# Arachnio.net
KiCad netlist of a schematic drawn in EAGLE
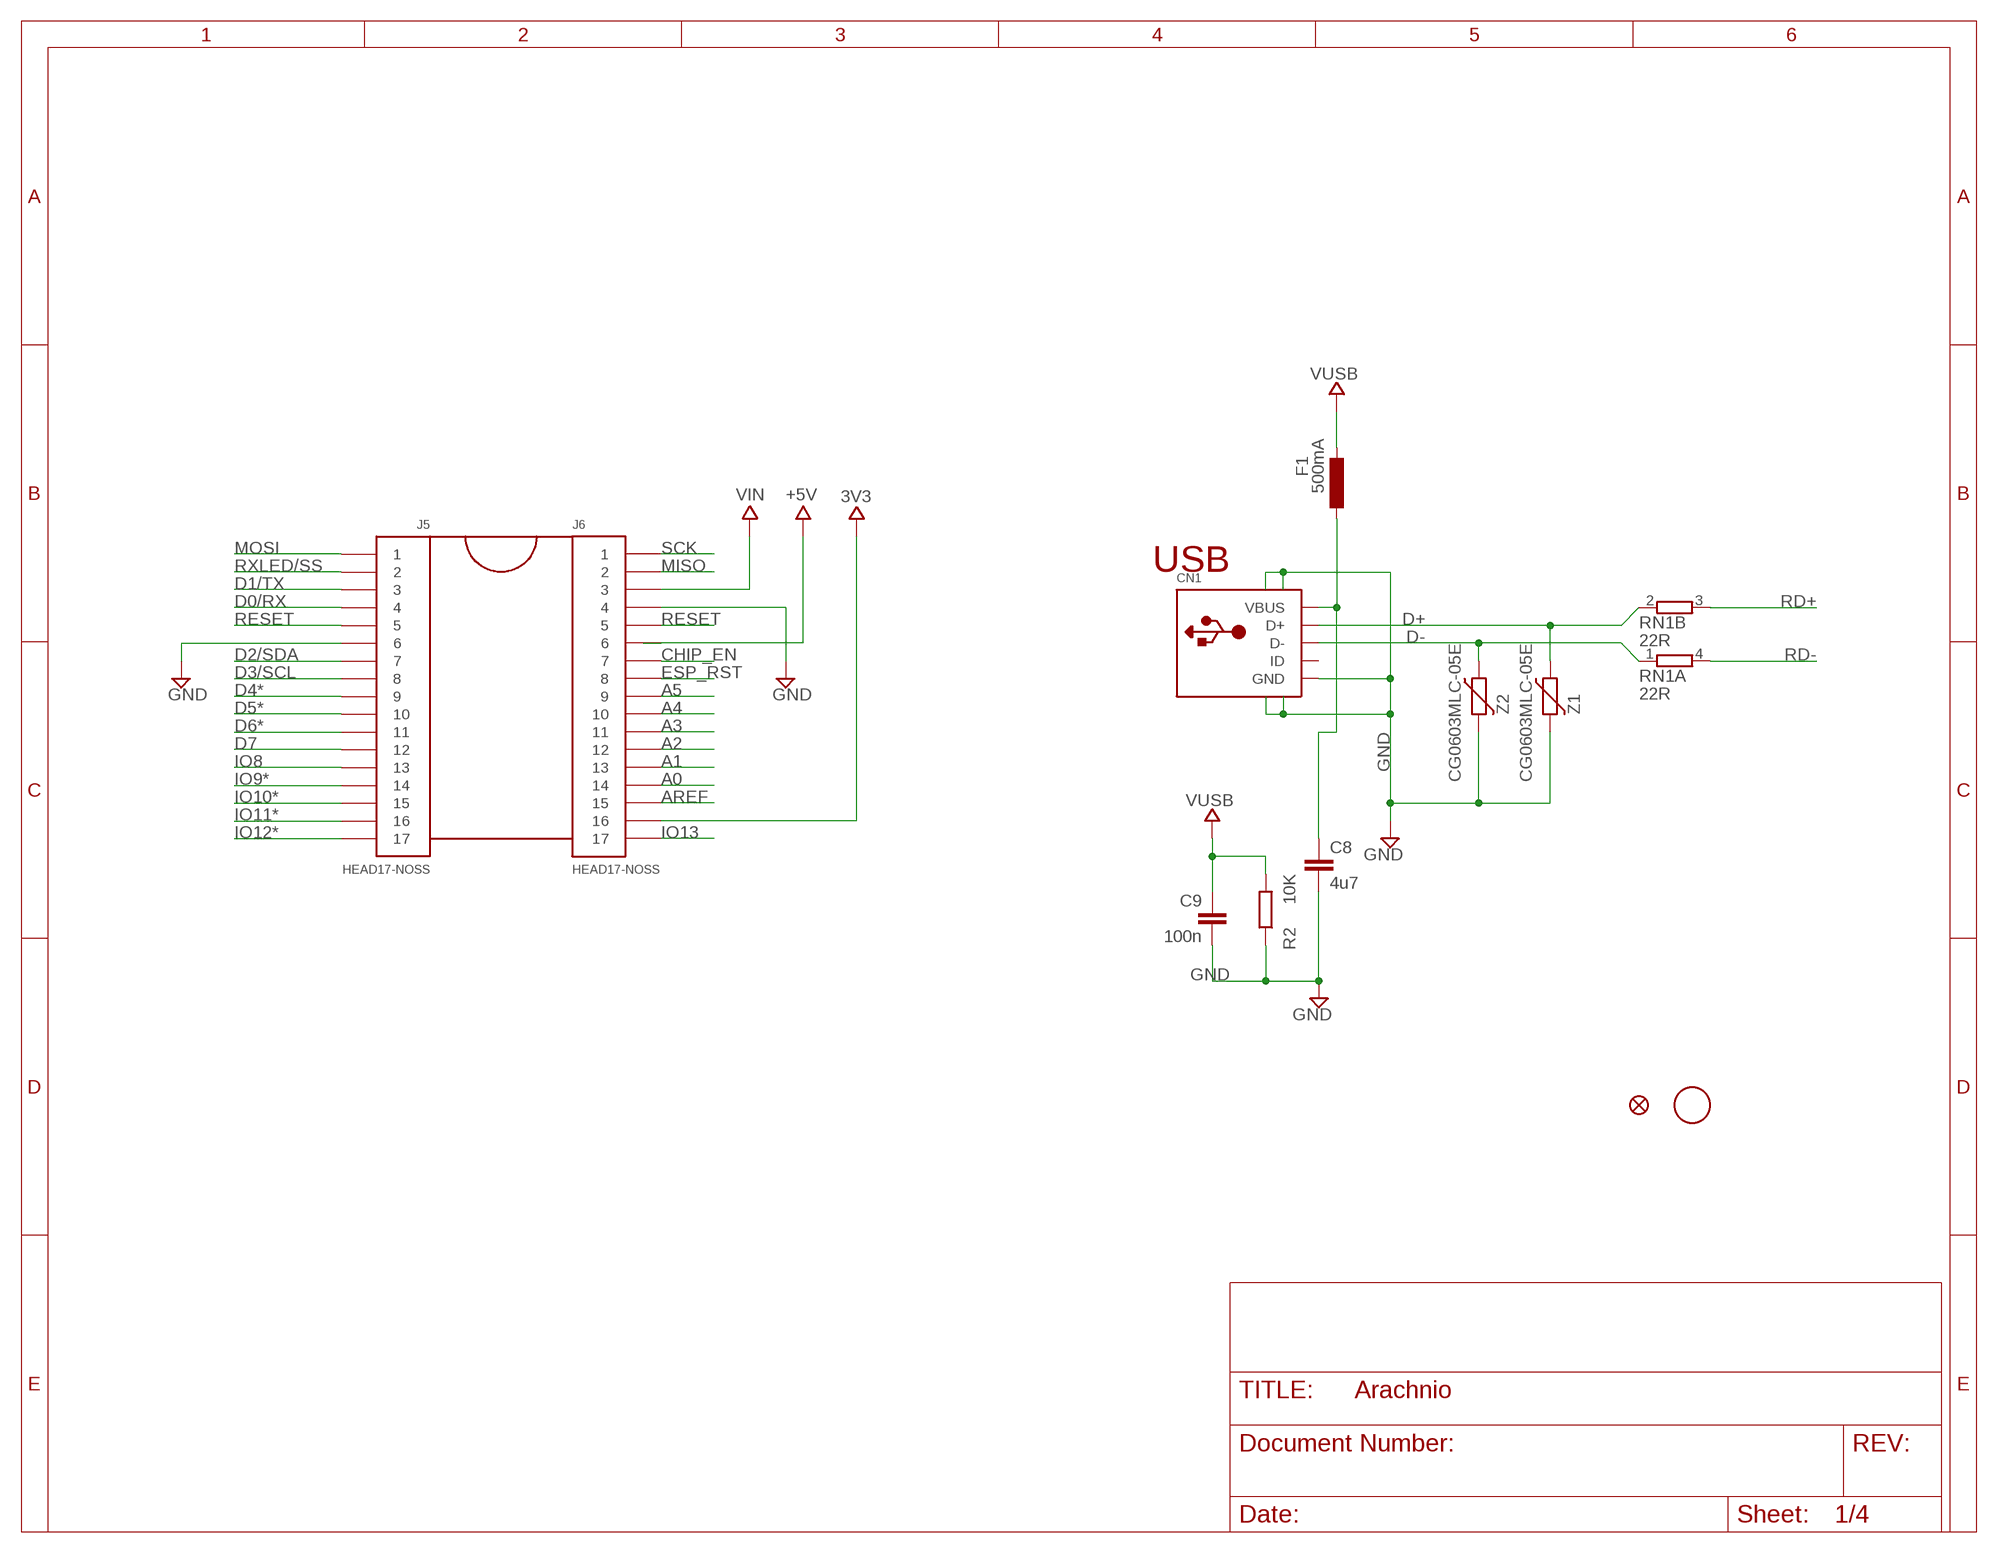
[diagram p0: schematic, sheet 1]
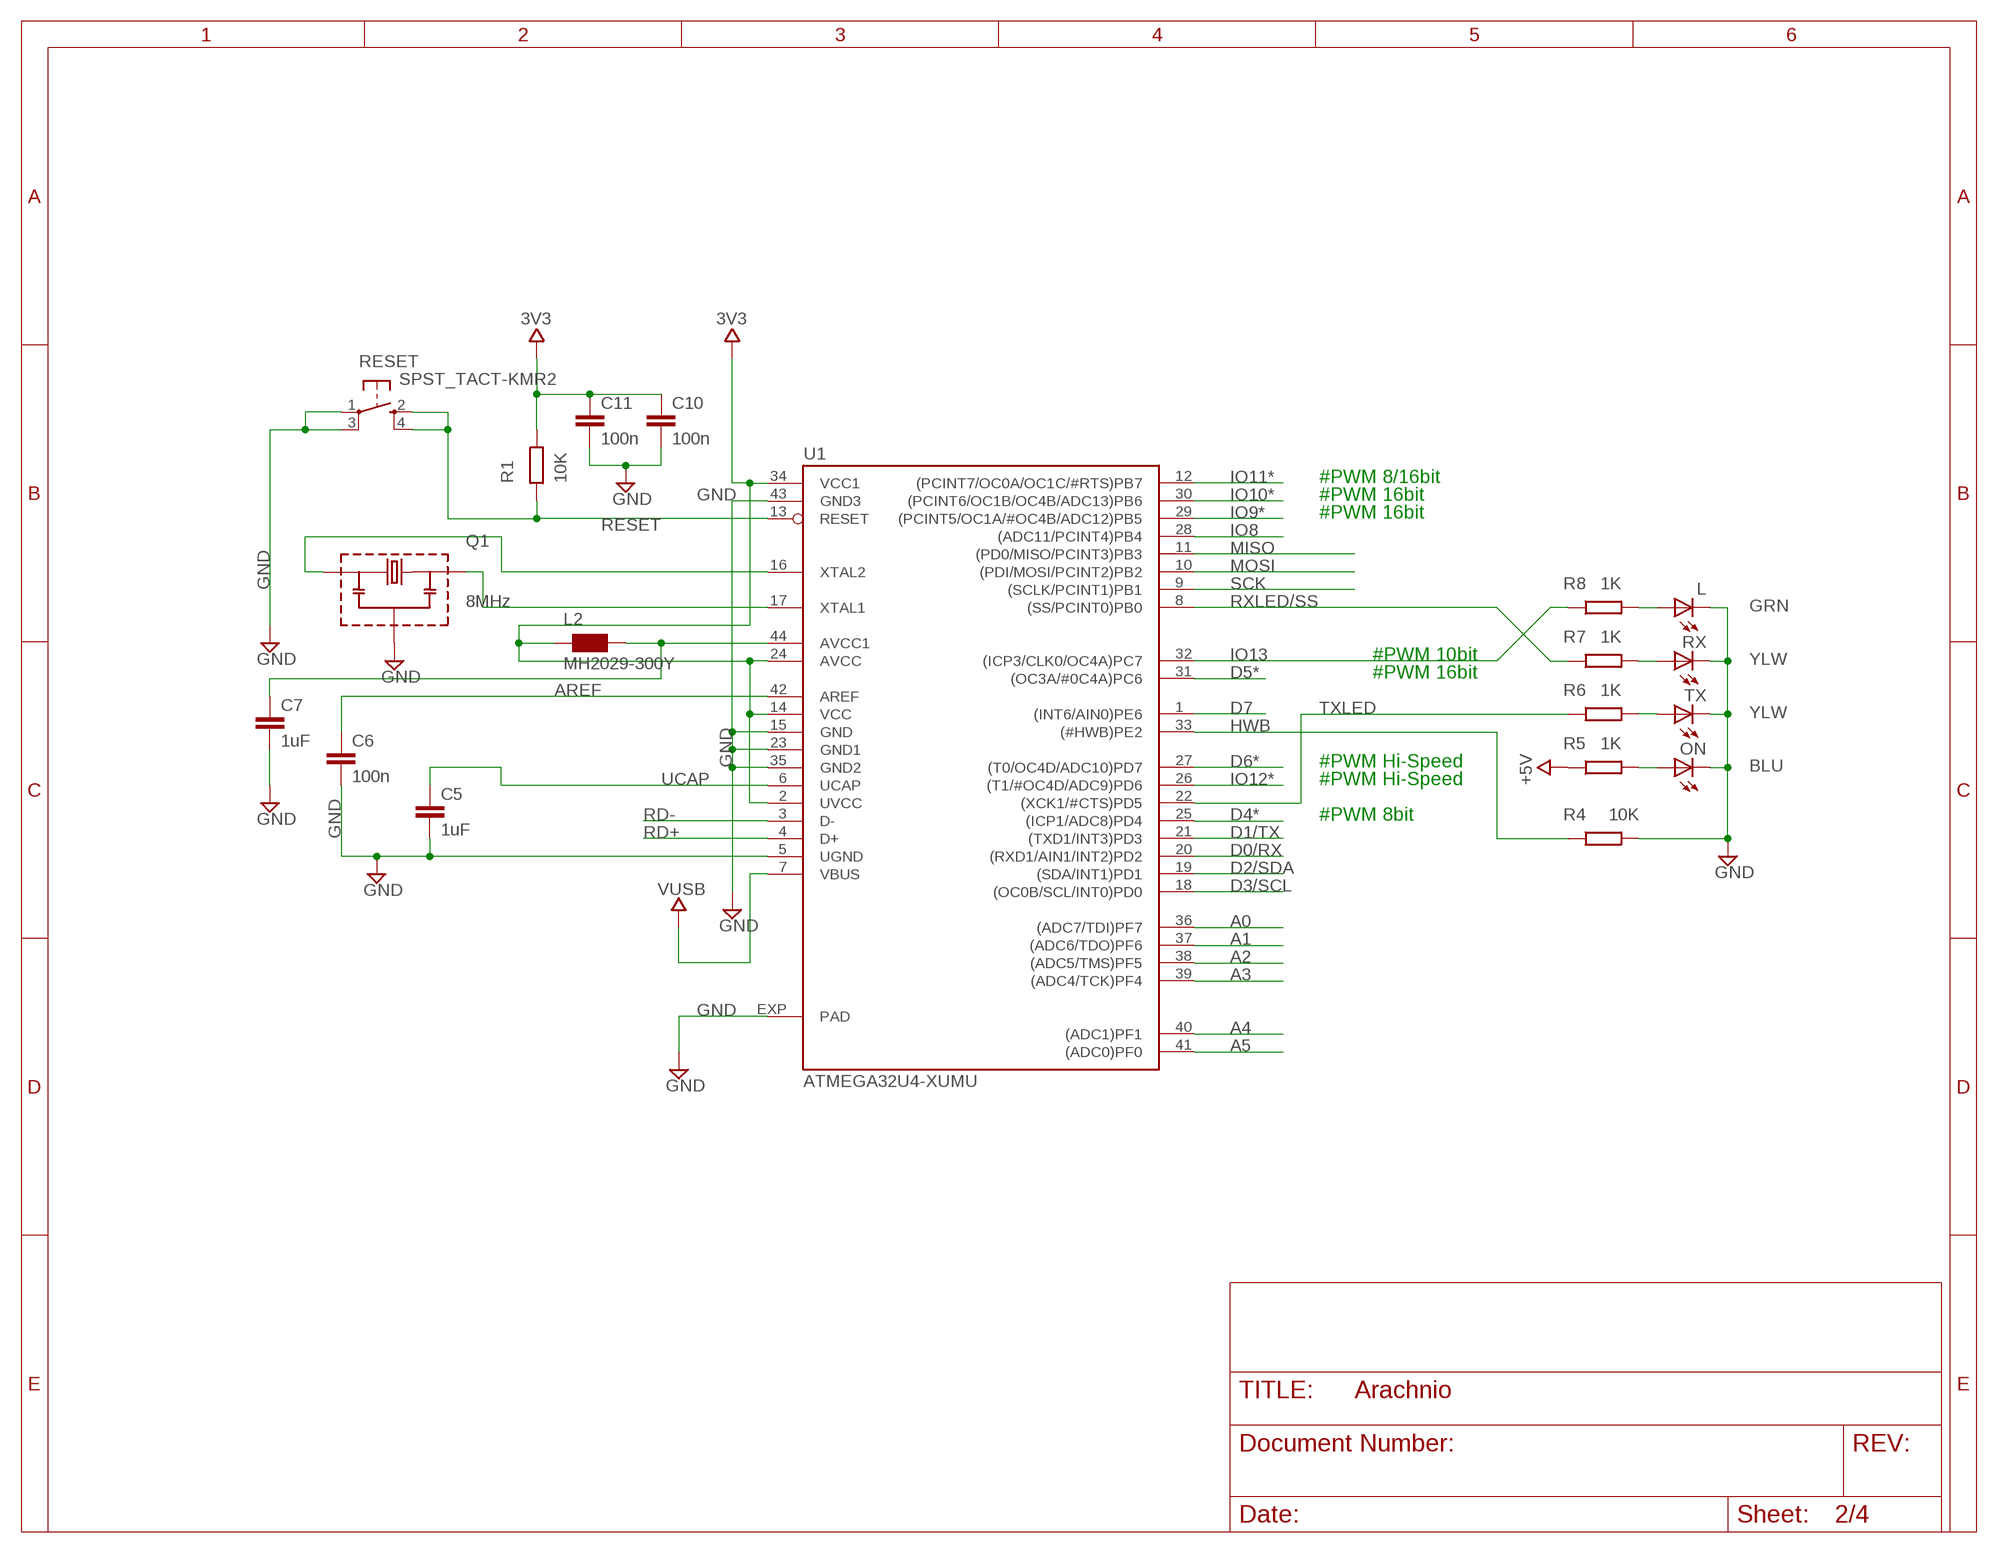
[diagram p1: schematic, sheet 2]
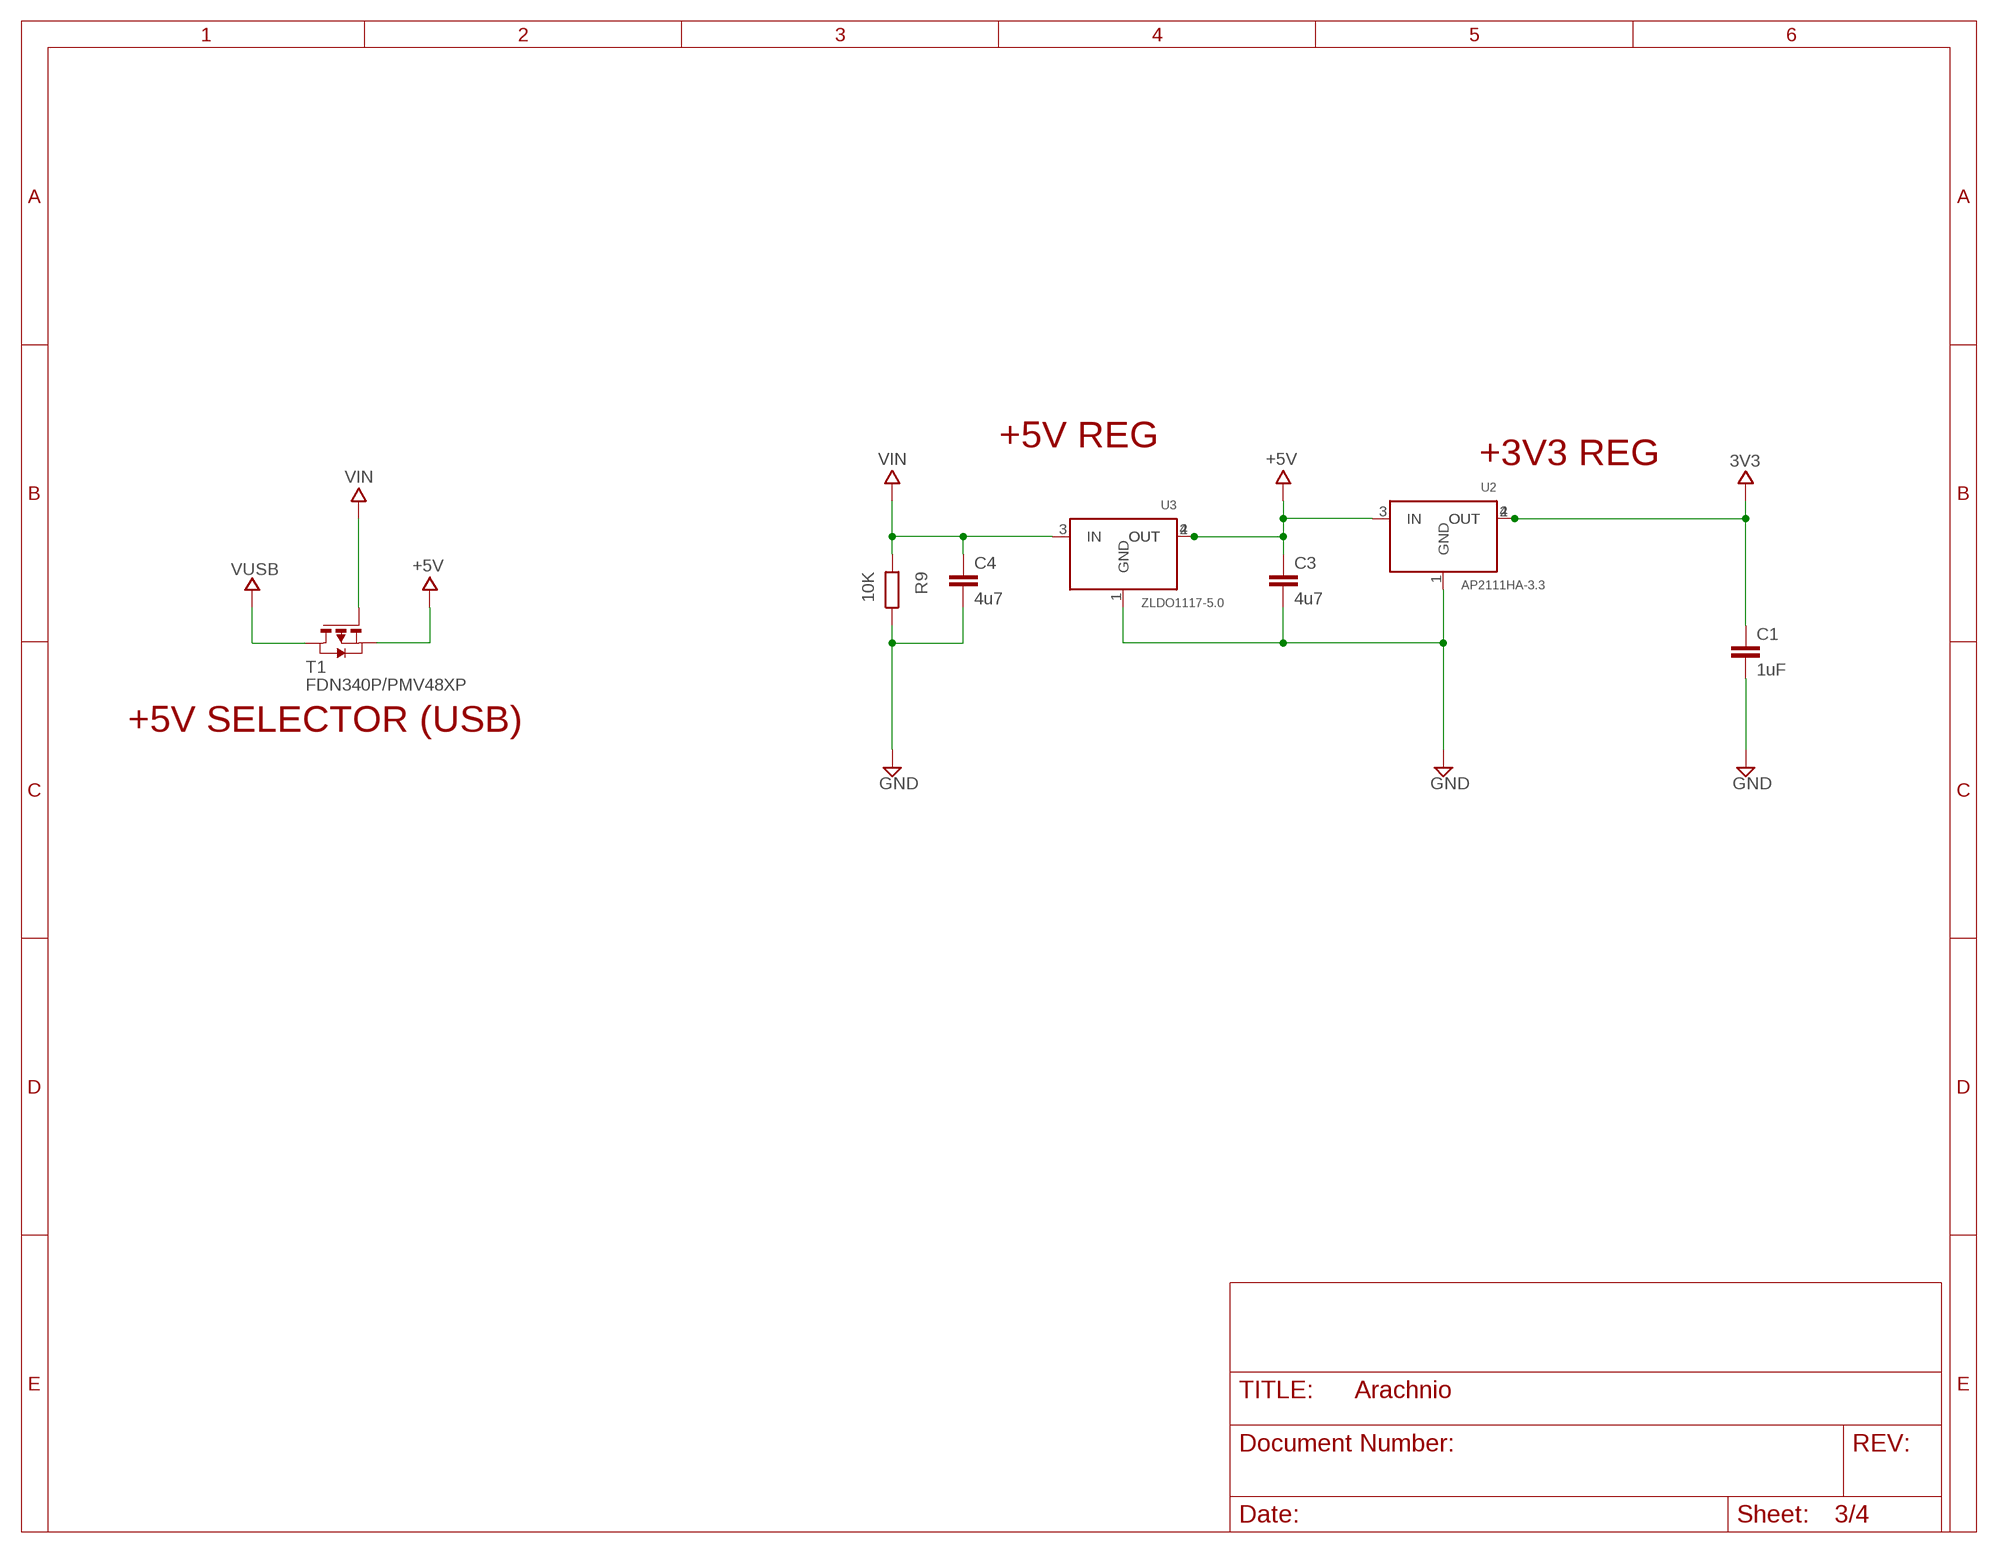
[diagram p2: schematic, sheet 3]
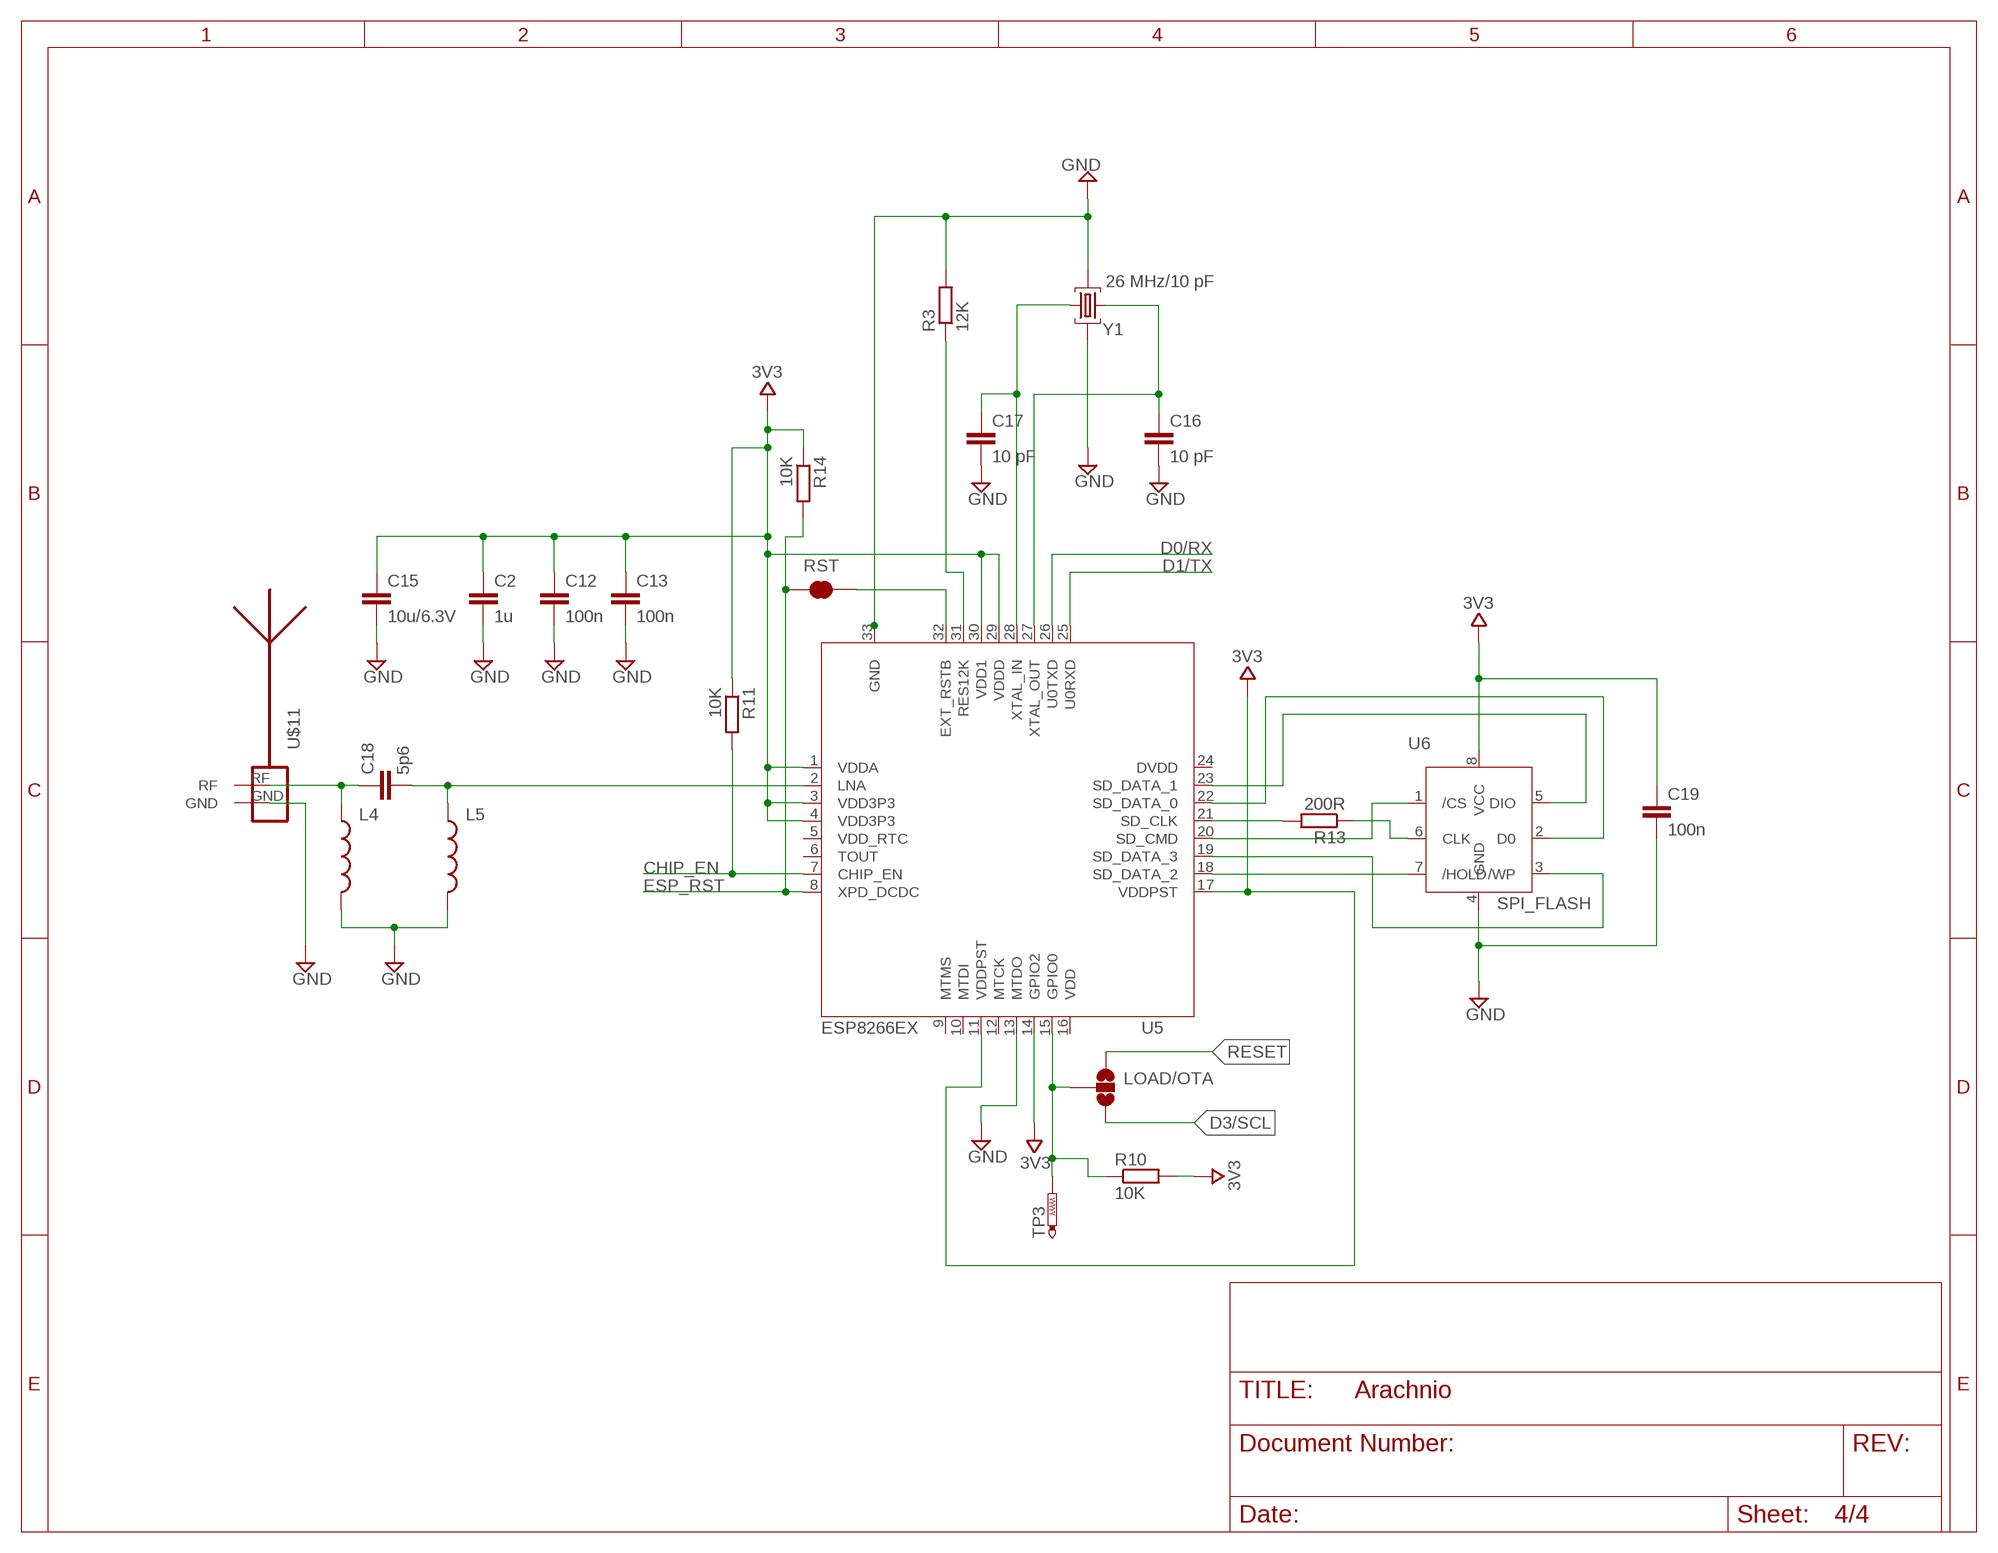
[diagram p3: schematic, sheet 4]

(export (version "E")
  (design (tool "Eeschema 10.0.6"))
  (components
    (comp (ref "C1")
      (value "1uF")
      (footprint "eagle-import:C0603")
      (fields (field (name "PARTNO") "C0603C105K3PACTU"))
      (libsource (lib "eagle-import") (part "C-EUC0603"))
    )
    (comp (ref "C3")
      (value "4u7")
      (footprint "eagle-import:C0603")
      (fields (field (name "PARTNO") "CL10A475KA8NQNC"))
      (libsource (lib "eagle-import") (part "C-EUC0603"))
    )
    (comp (ref "C4")
      (value "4u7")
      (footprint "eagle-import:C0603")
      (fields (field (name "PARTNO") "CL10A475KA8NQNC"))
      (libsource (lib "eagle-import") (part "C-EUC0603"))
    )
    (comp (ref "R9")
      (value "10K")
      (footprint "eagle-import:R0603")
      (fields (field (name "PARTNO") "RNCP0603FTD10K0"))
      (libsource (lib "eagle-import") (part "R-EU_R0603"))
    )
    (comp (ref "T1")
      (value "FDN340P/PMV48XP")
      (footprint "eagle-import:SOT-23")
      (fields (field (name "PARTNO") "FDN340P"))
      (libsource (lib "eagle-import") (part "PMOSSOT23"))
    )
    (comp (ref "U2")
      (value "AP2111HA-3.3")
      (footprint "eagle-import:SOT223")
      (fields (field (name "PARTNO") "AP2111H-3.3TRG1"))
      (libsource (lib "eagle-import") (part "AP2111HA-3.3"))
    )
    (comp (ref "U3")
      (value "ZLDO1117-5.0")
      (footprint "eagle-import:SOT223")
      (fields (field (name "PARTNO") "ZLDO1117G50TA"))
      (libsource (lib "eagle-import") (part "ZLDO1117-5.0"))
    )
    (comp (ref "C2")
      (value "1u")
      (footprint "eagle-import:C0603")
      (fields (field (name "PARTNO") "C0603C105K3PACTU"))
      (libsource (lib "eagle-import") (part "C-EUC0603"))
    )
    (comp (ref "C12")
      (value "100n")
      (footprint "eagle-import:C0603")
      (fields (field (name "PARTNO") "CC0603ZRY5V9BB104"))
      (libsource (lib "eagle-import") (part "C-EUC0603"))
    )
    (comp (ref "C13")
      (value "100n")
      (footprint "eagle-import:C0603")
      (fields (field (name "PARTNO") "CC0603ZRY5V9BB104"))
      (libsource (lib "eagle-import") (part "C-EUC0603"))
    )
    (comp (ref "C15")
      (value "10u/6.3V")
      (footprint "eagle-import:C0603")
      (fields (field (name "PARTNO") "JMK107ABJ106MAHT"))
      (libsource (lib "eagle-import") (part "C-EUC0603"))
    )
    (comp (ref "C16")
      (value "10 pF")
      (footprint "eagle-import:C0603")
      (fields (field (name "PARTNO") "C0603C100K5GACTU"))
      (libsource (lib "eagle-import") (part "C-EUC0603"))
    )
    (comp (ref "C17")
      (value "10 pF")
      (footprint "eagle-import:C0603")
      (fields (field (name "PARTNO") "C0603C100K5GACTU"))
      (libsource (lib "eagle-import") (part "C-EUC0603"))
    )
    (comp (ref "C18")
      (value "5p6")
      (footprint "eagle-import:C0603")
      (fields (field (name "PARTNO") "251R14S5R6CV4T"))
      (libsource (lib "eagle-import") (part "C-EUC0603"))
    )
    (comp (ref "C19")
      (value "100n")
      (footprint "eagle-import:C0603")
      (fields (field (name "PARTNO") "CC0603ZRY5V9BB104"))
      (libsource (lib "eagle-import") (part "C-EUC0603"))
    )
    (comp (ref "L4")
      (value "INDUCTOR0603")
      (footprint "eagle-import:0603")
      (libsource (lib "eagle-import") (part "INDUCTOR0603"))
    )
    (comp (ref "L5")
      (value "INDUCTOR0603")
      (footprint "eagle-import:0603")
      (libsource (lib "eagle-import") (part "INDUCTOR0603"))
    )
    (comp (ref "LOAD/OTA")
      (value "JUMPER-PAD-3-NOYES_SILK")
      (footprint "eagle-import:PAD-JUMPER-3-NO_YES_SILK")
      (libsource (lib "eagle-import") (part "JUMPER-PAD-3-NOYES_SILK"))
    )
    (comp (ref "R3")
      (value "12K")
      (footprint "eagle-import:R0603")
      (fields (field (name "PARTNO") "RMCF0603FT12K0"))
      (libsource (lib "eagle-import") (part "R-EU_R0603"))
    )
    (comp (ref "R10")
      (value "10K")
      (footprint "eagle-import:R0603")
      (fields (field (name "PARTNO") "RNCP0603FTD10K0"))
      (libsource (lib "eagle-import") (part "R-EU_R0603"))
    )
    (comp (ref "R11")
      (value "10K")
      (footprint "eagle-import:R0603")
      (fields (field (name "PARTNO") "RNCP0603FTD10K0"))
      (libsource (lib "eagle-import") (part "R-EU_R0603"))
    )
    (comp (ref "R13")
      (value "200R")
      (footprint "eagle-import:R0603")
      (fields (field (name "PARTNO") "MCR03ERTJ201"))
      (libsource (lib "eagle-import") (part "R-EU_R0603"))
    )
    (comp (ref "R14")
      (value "10K")
      (footprint "eagle-import:R0603")
      (fields (field (name "PARTNO") "RNCP0603FTD10K0"))
      (libsource (lib "eagle-import") (part "R-EU_R0603"))
    )
    (comp (ref "RST")
      (value "JUMPER-PAD-2-NC_BY_TRACE")
      (footprint "eagle-import:PAD-JUMPER-2-NC_BY_TRACE_YES_SILK")
      (libsource (lib "eagle-import") (part "JUMPER-PAD-2-NC_BY_TRACE"))
    )
    (comp (ref "TP3")
      (value "PTR1TP15SQ")
      (footprint "eagle-import:TP15SQ")
      (libsource (lib "eagle-import") (part "PTR1TP15SQ"))
    )
    (comp (ref "U$11")
      (value "ANTENNA_1RIGHT")
      (footprint "eagle-import:SWRA117D_RIGHT")
      (libsource (lib "eagle-import") (part "ANTENNA_1RIGHT"))
    )
    (comp (ref "U5")
      (value "ESP8266EX")
      (footprint "eagle-import:QFN32")
      (libsource (lib "eagle-import") (part "ESP8266EX"))
    )
    (comp (ref "U6")
      (value "SPI_FLASH")
      (footprint "eagle-import:SOIC-8")
      (fields (field (name "PARTNO") "SST25VF512A-33-4C-SAE"))
      (libsource (lib "eagle-import") (part "SPI_FLASH"))
    )
    (comp (ref "Y1")
      (value "26 MHz/10 pF")
      (footprint "eagle-import:CRYSTAL-3.2-2.5")
      (fields (field (name "PARTNO") "403C11A26M00000"))
      (libsource (lib "eagle-import") (part "CRYSTAL-3.2-2.5"))
    )
    (comp (ref "C5")
      (value "1uF")
      (footprint "eagle-import:C0603")
      (fields (field (name "PARTNO") "C0603C105K3PACTU"))
      (libsource (lib "eagle-import") (part "C-EUC0603"))
    )
    (comp (ref "C6")
      (value "100n")
      (footprint "eagle-import:C0603")
      (fields (field (name "PARTNO") "CC0603ZRY5V9BB104"))
      (libsource (lib "eagle-import") (part "C-EUC0603"))
    )
    (comp (ref "C7")
      (value "1uF")
      (footprint "eagle-import:C0603")
      (fields (field (name "PARTNO") "C0603C105K3PACTU"))
      (libsource (lib "eagle-import") (part "C-EUC0603"))
    )
    (comp (ref "C10")
      (value "100n")
      (footprint "eagle-import:C0603")
      (fields (field (name "PARTNO") "CC0603ZRY5V9BB104"))
      (libsource (lib "eagle-import") (part "C-EUC0603"))
    )
    (comp (ref "C11")
      (value "100n")
      (footprint "eagle-import:C0603")
      (fields (field (name "PARTNO") "CC0603ZRY5V9BB104"))
      (libsource (lib "eagle-import") (part "C-EUC0603"))
    )
    (comp (ref "L")
      (value "GRN")
      (footprint "eagle-import:CHIP-LED0603")
      (fields (field (name "PARTNO") "LTST-C191KGKT"))
      (libsource (lib "eagle-import") (part "LEDCHIP-LED0603"))
    )
    (comp (ref "L2")
      (value "MH2029-300Y")
      (footprint "eagle-import:0805")
      (libsource (lib "eagle-import") (part "WE-CBF_0805"))
    )
    (comp (ref "ON")
      (value "BLU")
      (footprint "eagle-import:CHIP-LED0603")
      (fields (field (name "PARTNO") "LB Q39G-L2N2-35-1"))
      (libsource (lib "eagle-import") (part "LEDCHIP-LED0603"))
    )
    (comp (ref "Q1")
      (value "8MHz")
      (footprint "eagle-import:PRQC")
      (fields (field (name "PARTNO") "PRQC8.00CR1010V00L"))
      (libsource (lib "eagle-import") (part "PRQC"))
    )
    (comp (ref "R1")
      (value "10K")
      (footprint "eagle-import:R0603")
      (fields (field (name "PARTNO") "RNCP0603FTD10K0"))
      (libsource (lib "eagle-import") (part "R-EU_R0603"))
    )
    (comp (ref "R4")
      (value "10K")
      (footprint "eagle-import:R0603")
      (fields (field (name "PARTNO") "RNCP0603FTD10K0"))
      (libsource (lib "eagle-import") (part "R-EU_R0603"))
    )
    (comp (ref "R5")
      (value "1K")
      (footprint "eagle-import:R0603")
      (fields (field (name "PARTNO") "RMCF0603FT1K00"))
      (libsource (lib "eagle-import") (part "R-EU_R0603"))
    )
    (comp (ref "R6")
      (value "1K")
      (footprint "eagle-import:R0603")
      (fields (field (name "PARTNO") "RMCF0603FT1K00"))
      (libsource (lib "eagle-import") (part "R-EU_R0603"))
    )
    (comp (ref "R7")
      (value "1K")
      (footprint "eagle-import:R0603")
      (fields (field (name "PARTNO") "RMCF0603FT1K00"))
      (libsource (lib "eagle-import") (part "R-EU_R0603"))
    )
    (comp (ref "R8")
      (value "1K")
      (footprint "eagle-import:R0603")
      (fields (field (name "PARTNO") "RMCF0603FT1K00"))
      (libsource (lib "eagle-import") (part "R-EU_R0603"))
    )
    (comp (ref "RESET")
      (value "SPST_TACT-KMR2")
      (footprint "eagle-import:KMR2")
      (fields (field (name "PARTNO") "KMR221NG"))
      (libsource (lib "eagle-import") (part "SPST_TACT-KMR2"))
    )
    (comp (ref "RX")
      (value "YLW")
      (footprint "eagle-import:CHIP-LED0603")
      (fields (field (name "PARTNO") "LTST-C191KSKT"))
      (libsource (lib "eagle-import") (part "LEDCHIP-LED0603"))
    )
    (comp (ref "TX")
      (value "YLW")
      (footprint "eagle-import:CHIP-LED0603")
      (fields (field (name "PARTNO") "LTST-C191KSKT"))
      (libsource (lib "eagle-import") (part "LEDCHIP-LED0603"))
    )
    (comp (ref "U1")
      (value "ATMEGA32U4-XUMU")
      (footprint "eagle-import:QFN44ML7X7")
      (fields (field (name "PARTNO") "ATMEGA32U4-MU"))
      (libsource (lib "eagle-import") (part "ATMEGA32U4-XUMU"))
    )
    (comp (ref "C8")
      (value "4u7")
      (footprint "eagle-import:C0603")
      (fields (field (name "PARTNO") "CL10A475KA8NQNC"))
      (libsource (lib "eagle-import") (part "C-EUC0603"))
    )
    (comp (ref "C9")
      (value "100n")
      (footprint "eagle-import:C0603")
      (fields (field (name "PARTNO") "CC0603ZRY5V9BB104"))
      (libsource (lib "eagle-import") (part "C-EUC0603"))
    )
    (comp (ref "CN1")
      (value "USBMINIB")
      (footprint "eagle-import:USB-MINIB")
      (fields (field (name "PARTNO") "USB-M26FTR"))
      (libsource (lib "eagle-import") (part "USBMINIB"))
    )
    (comp (ref "F1")
      (value "500mA")
      (footprint "eagle-import:L1812")
      (fields (field (name "PARTNO") "MF-MSMF050-2"))
      (libsource (lib "eagle-import") (part "L-EUL1812"))
    )
    (comp (ref "J5")
      (value "HEAD17-NOSS")
      (footprint "eagle-import:HEAD17-NOSS")
      (fields (field (name "PARTNO") "PREC017SAAN-RC"))
      (libsource (lib "eagle-import") (part "HEAD17-NOSS"))
    )
    (comp (ref "J6")
      (value "HEAD17-NOSS")
      (footprint "eagle-import:HEAD17-NOSS-1")
      (fields (field (name "PARTNO") "PREC017SAAN-RC"))
      (libsource (lib "eagle-import") (part "HEAD17-NOSS-1"))
    )
    (comp (ref "R2")
      (value "10K")
      (footprint "eagle-import:R0603")
      (fields (field (name "PARTNO") "RNCP0603FTD10K0"))
      (libsource (lib "eagle-import") (part "R-EU_R0603"))
    )
    (comp (ref "RN1")
      (value "22R")
      (footprint "eagle-import:EXBV4V")
      (fields (field (name "PARTNO") "EXB-V4V220JV"))
      (libsource (lib "eagle-import") (part "2R-NEXBV4V"))
    )
    (comp (ref "U$37")
      (value "FIDUCIALMOUNT")
      (footprint "eagle-import:FIDUCIA-MOUNT")
      (libsource (lib "eagle-import") (part "FIDUCIALMOUNT"))
    )
    (comp (ref "U$53")
      (value "FIDUCIAL1X2")
      (footprint "eagle-import:FIDUCIAL-1X2")
      (libsource (lib "eagle-import") (part "FIDUCIAL1X2"))
    )
    (comp (ref "Z1")
      (value "CG0603MLC-05E")
      (footprint "eagle-import:CT_CN0603")
      (libsource (lib "eagle-import") (part "VARISTORCN0603"))
    )
    (comp (ref "Z2")
      (value "CG0603MLC-05E")
      (footprint "eagle-import:CT_CN0603")
      (libsource (lib "eagle-import") (part "VARISTORCN0603"))
    )
  )
  (nets
    (net (code "1") (name "+5V") (class "Default")
      (node (ref "C3") (pin "1") (pinfunction "1_1") (pintype "passive"))
      (node (ref "J6") (pin "6") (pinfunction "6_6") (pintype "passive"))
      (node (ref "R5") (pin "1") (pinfunction "1_1") (pintype "passive"))
      (node (ref "T1") (pin "2") (pinfunction "S_2") (pintype "passive"))
      (node (ref "U2") (pin "3") (pinfunction "IN_3") (pintype "bidirectional"))
      (node (ref "U3") (pin "2") (pinfunction "OUT_2") (pintype "bidirectional"))
      (node (ref "U3") (pin "4") (pinfunction "OUT_4") (pintype "bidirectional"))
    )
    (net (code "2") (name "3V3") (class "Default")
      (node (ref "C1") (pin "1") (pinfunction "1_1") (pintype "passive"))
      (node (ref "C10") (pin "1") (pinfunction "1_1") (pintype "passive"))
      (node (ref "C11") (pin "1") (pinfunction "1_1") (pintype "passive"))
      (node (ref "C12") (pin "1") (pinfunction "1_1") (pintype "passive"))
      (node (ref "C13") (pin "1") (pinfunction "1_1") (pintype "passive"))
      (node (ref "C15") (pin "1") (pinfunction "1_1") (pintype "passive"))
      (node (ref "C19") (pin "1") (pinfunction "1_1") (pintype "passive"))
      (node (ref "C2") (pin "1") (pinfunction "1_1") (pintype "passive"))
      (node (ref "J6") (pin "16") (pinfunction "16_16") (pintype "passive"))
      (node (ref "L2") (pin "1") (pinfunction "1_1") (pintype "passive"))
      (node (ref "R1") (pin "1") (pinfunction "1_1") (pintype "passive"))
      (node (ref "R10") (pin "2") (pinfunction "2_2") (pintype "passive"))
      (node (ref "R11") (pin "1") (pinfunction "1_1") (pintype "passive"))
      (node (ref "R14") (pin "1") (pinfunction "1_1") (pintype "passive"))
      (node (ref "U1") (pin "14") (pinfunction "VCC_14") (pintype "power_in"))
      (node (ref "U1") (pin "2") (pinfunction "UVCC_2") (pintype "power_in"))
      (node (ref "U1") (pin "24") (pinfunction "AVCC_24") (pintype "power_in"))
      (node (ref "U1") (pin "34") (pinfunction "VCC1_34") (pintype "power_in"))
      (node (ref "U2") (pin "2") (pinfunction "OUT_2") (pintype "bidirectional"))
      (node (ref "U2") (pin "4") (pinfunction "OUT_4") (pintype "bidirectional"))
      (node (ref "U5") (pin "1") (pinfunction "VDDA_1") (pintype "power_in"))
      (node (ref "U5") (pin "11") (pinfunction "VDDPST_11") (pintype "power_in"))
      (node (ref "U5") (pin "14") (pinfunction "GPIO2_14") (pintype "bidirectional"))
      (node (ref "U5") (pin "17") (pinfunction "VDDPST_17") (pintype "power_in"))
      (node (ref "U5") (pin "29") (pinfunction "VDDD_29") (pintype "power_in"))
      (node (ref "U5") (pin "3") (pinfunction "VDD3P3_3") (pintype "power_in"))
      (node (ref "U5") (pin "30") (pinfunction "VDD1_30") (pintype "power_in"))
      (node (ref "U5") (pin "4") (pinfunction "VDD3P3_4") (pintype "power_in"))
      (node (ref "U6") (pin "8") (pinfunction "VCC_8") (pintype "power_in"))
    )
    (net (code "3") (name "A0") (class "Default")
      (node (ref "J6") (pin "14") (pinfunction "14_14") (pintype "passive"))
      (node (ref "U1") (pin "36") (pinfunction "(ADC7/TDI)PF7_36") (pintype "bidirectional"))
    )
    (net (code "4") (name "A1") (class "Default")
      (node (ref "J6") (pin "13") (pinfunction "13_13") (pintype "passive"))
      (node (ref "U1") (pin "37") (pinfunction "(ADC6/TDO)PF6_37") (pintype "bidirectional"))
    )
    (net (code "5") (name "A2") (class "Default")
      (node (ref "J6") (pin "12") (pinfunction "12_12") (pintype "passive"))
      (node (ref "U1") (pin "38") (pinfunction "(ADC5/TMS)PF5_38") (pintype "bidirectional"))
    )
    (net (code "6") (name "A3") (class "Default")
      (node (ref "J6") (pin "11") (pinfunction "11_11") (pintype "passive"))
      (node (ref "U1") (pin "39") (pinfunction "(ADC4/TCK)PF4_39") (pintype "bidirectional"))
    )
    (net (code "7") (name "A4") (class "Default")
      (node (ref "J6") (pin "10") (pinfunction "10_10") (pintype "passive"))
      (node (ref "U1") (pin "40") (pinfunction "(ADC1)PF1_40") (pintype "bidirectional"))
    )
    (net (code "8") (name "A5") (class "Default")
      (node (ref "J6") (pin "9") (pinfunction "9_9") (pintype "passive"))
      (node (ref "U1") (pin "41") (pinfunction "(ADC0)PF0_41") (pintype "bidirectional"))
    )
    (net (code "9") (name "AREF") (class "Default")
      (node (ref "C6") (pin "1") (pinfunction "1_1") (pintype "passive"))
      (node (ref "J6") (pin "15") (pinfunction "15_15") (pintype "passive"))
      (node (ref "U1") (pin "42") (pinfunction "AREF_42") (pintype "power_in"))
    )
    (net (code "10") (name "CHIP_EN") (class "Default")
      (node (ref "J6") (pin "7") (pinfunction "7_7") (pintype "passive"))
      (node (ref "R11") (pin "2") (pinfunction "2_2") (pintype "passive"))
      (node (ref "U5") (pin "7") (pinfunction "CHIP_EN_7") (pintype "input"))
    )
    (net (code "11") (name "D+") (class "Default")
      (node (ref "CN1") (pin "D+") (pinfunction "D+_D+") (pintype "bidirectional"))
      (node (ref "RN1") (pin "2") (pinfunction "1_2") (pintype "passive"))
      (node (ref "Z1") (pin "1") (pinfunction "1_1") (pintype "passive"))
    )
    (net (code "12") (name "D-") (class "Default")
      (node (ref "CN1") (pin "D-") (pinfunction "D-_D-") (pintype "bidirectional"))
      (node (ref "RN1") (pin "1") (pinfunction "1_1") (pintype "passive"))
      (node (ref "Z2") (pin "1") (pinfunction "1_1") (pintype "passive"))
    )
    (net (code "13") (name "D0{slash}RX") (class "Default")
      (node (ref "J5") (pin "4") (pinfunction "4_4") (pintype "passive"))
      (node (ref "U1") (pin "20") (pinfunction "(RXD1/AIN1/INT2)PD2_20") (pintype "bidirectional"))
      (node (ref "U5") (pin "26") (pinfunction "U0TXD_26") (pintype "bidirectional"))
    )
    (net (code "14") (name "D1{slash}TX") (class "Default")
      (node (ref "J5") (pin "3") (pinfunction "3_3") (pintype "passive"))
      (node (ref "U1") (pin "21") (pinfunction "(TXD1/INT3)PD3_21") (pintype "bidirectional"))
      (node (ref "U5") (pin "25") (pinfunction "U0RXD_25") (pintype "bidirectional"))
    )
    (net (code "15") (name "D2{slash}SDA") (class "Default")
      (node (ref "J5") (pin "7") (pinfunction "7_7") (pintype "passive"))
      (node (ref "U1") (pin "19") (pinfunction "(SDA/INT1)PD1_19") (pintype "bidirectional"))
    )
    (net (code "16") (name "D3{slash}SCL") (class "Default")
      (node (ref "J5") (pin "8") (pinfunction "8_8") (pintype "passive"))
      (node (ref "LOAD/OTA") (pin "3") (pinfunction "3_3") (pintype "passive"))
      (node (ref "U1") (pin "18") (pinfunction "(OC0B/SCL/INT0)PD0_18") (pintype "bidirectional"))
    )
    (net (code "17") (name "D4*") (class "Default")
      (node (ref "J5") (pin "9") (pinfunction "9_9") (pintype "passive"))
      (node (ref "U1") (pin "25") (pinfunction "(ICP1/ADC8)PD4_25") (pintype "bidirectional"))
    )
    (net (code "18") (name "D5*") (class "Default")
      (node (ref "J5") (pin "10") (pinfunction "10_10") (pintype "passive"))
      (node (ref "U1") (pin "31") (pinfunction "(OC3A/#0C4A)PC6_31") (pintype "bidirectional"))
    )
    (net (code "19") (name "D6*") (class "Default")
      (node (ref "J5") (pin "11") (pinfunction "11_11") (pintype "passive"))
      (node (ref "U1") (pin "27") (pinfunction "(T0/OC4D/ADC10)PD7_27") (pintype "bidirectional"))
    )
    (net (code "20") (name "D7") (class "Default")
      (node (ref "J5") (pin "12") (pinfunction "12_12") (pintype "passive"))
      (node (ref "U1") (pin "1") (pinfunction "(INT6/AIN0)PE6_1") (pintype "bidirectional"))
    )
    (net (code "21") (name "DVDD") (class "Default")
      (node (ref "U5") (pin "24") (pinfunction "DVDD_24") (pintype "power_in"))
    )
    (net (code "22") (name "ESP_RST") (class "Default")
      (node (ref "J6") (pin "8") (pinfunction "8_8") (pintype "passive"))
      (node (ref "R14") (pin "2") (pinfunction "2_2") (pintype "passive"))
      (node (ref "RST") (pin "1") (pinfunction "1_1") (pintype "passive"))
      (node (ref "U5") (pin "8") (pinfunction "XPD_DCDC_8") (pintype "bidirectional"))
    )
    (net (code "23") (name "GND") (class "Default")
      (node (ref "C1") (pin "2") (pinfunction "2_2") (pintype "passive"))
      (node (ref "C10") (pin "2") (pinfunction "2_2") (pintype "passive"))
      (node (ref "C11") (pin "2") (pinfunction "2_2") (pintype "passive"))
      (node (ref "C12") (pin "2") (pinfunction "2_2") (pintype "passive"))
      (node (ref "C13") (pin "2") (pinfunction "2_2") (pintype "passive"))
      (node (ref "C15") (pin "2") (pinfunction "2_2") (pintype "passive"))
      (node (ref "C16") (pin "2") (pinfunction "2_2") (pintype "passive"))
      (node (ref "C17") (pin "2") (pinfunction "2_2") (pintype "passive"))
      (node (ref "C19") (pin "2") (pinfunction "2_2") (pintype "passive"))
      (node (ref "C2") (pin "2") (pinfunction "2_2") (pintype "passive"))
      (node (ref "C3") (pin "2") (pinfunction "2_2") (pintype "passive"))
      (node (ref "C4") (pin "2") (pinfunction "2_2") (pintype "passive"))
      (node (ref "C5") (pin "2") (pinfunction "2_2") (pintype "passive"))
      (node (ref "C6") (pin "2") (pinfunction "2_2") (pintype "passive"))
      (node (ref "C7") (pin "2") (pinfunction "2_2") (pintype "passive"))
      (node (ref "C8") (pin "2") (pinfunction "2_2") (pintype "passive"))
      (node (ref "C9") (pin "2") (pinfunction "2_2") (pintype "passive"))
      (node (ref "CN1") (pin "GND") (pinfunction "GND_GND") (pintype "power_in"))
      (node (ref "CN1") (pin "GND1") (pinfunction "SHIELD_GND1") (pintype "power_in"))
      (node (ref "CN1") (pin "GND2") (pinfunction "SHIELD_GND2") (pintype "power_in"))
      (node (ref "CN1") (pin "GND3") (pinfunction "SHIELD_GND3") (pintype "power_in"))
      (node (ref "CN1") (pin "GND4") (pinfunction "SHIELD_GND4") (pintype "power_in"))
      (node (ref "J5") (pin "6") (pinfunction "6_6") (pintype "passive"))
      (node (ref "J6") (pin "4") (pinfunction "4_4") (pintype "passive"))
      (node (ref "L") (pin "C") (pinfunction "C_C") (pintype "passive"))
      (node (ref "L4") (pin "2") (pinfunction "2_2") (pintype "passive"))
      (node (ref "L5") (pin "2") (pinfunction "2_2") (pintype "passive"))
      (node (ref "ON") (pin "C") (pinfunction "C_C") (pintype "passive"))
      (node (ref "Q1") (pin "P$2") (pinfunction "2_P$2") (pintype "passive"))
      (node (ref "R2") (pin "1") (pinfunction "1_1") (pintype "passive"))
      (node (ref "R3") (pin "2") (pinfunction "2_2") (pintype "passive"))
      (node (ref "R4") (pin "2") (pinfunction "2_2") (pintype "passive"))
      (node (ref "R9") (pin "1") (pinfunction "1_1") (pintype "passive"))
      (node (ref "RESET") (pin "1") (pinfunction "P_1") (pintype "passive"))
      (node (ref "RESET") (pin "3") (pinfunction "P1_3") (pintype "passive"))
      (node (ref "RX") (pin "C") (pinfunction "C_C") (pintype "passive"))
      (node (ref "TX") (pin "C") (pinfunction "C_C") (pintype "passive"))
      (node (ref "U$11") (pin "GND") (pinfunction "GND_GND") (pintype "passive"))
      (node (ref "U1") (pin "15") (pinfunction "GND_15") (pintype "power_in"))
      (node (ref "U1") (pin "23") (pinfunction "GND1_23") (pintype "power_in"))
      (node (ref "U1") (pin "35") (pinfunction "GND2_35") (pintype "power_in"))
      (node (ref "U1") (pin "43") (pinfunction "GND3_43") (pintype "power_in"))
      (node (ref "U1") (pin "5") (pinfunction "UGND_5") (pintype "power_in"))
      (node (ref "U1") (pin "EXP") (pinfunction "PAD_EXP") (pintype "power_in"))
      (node (ref "U2") (pin "1") (pinfunction "GND_1") (pintype "bidirectional"))
      (node (ref "U3") (pin "1") (pinfunction "GND_1") (pintype "bidirectional"))
      (node (ref "U5") (pin "13") (pinfunction "MTDO_13") (pintype "bidirectional"))
      (node (ref "U5") (pin "33") (pinfunction "GND_33") (pintype "power_in"))
      (node (ref "U6") (pin "4") (pinfunction "GND_4") (pintype "power_in"))
      (node (ref "Y1") (pin "2") (pinfunction "GND_2") (pintype "passive"))
      (node (ref "Y1") (pin "4") (pinfunction "GND_4") (pintype "passive"))
      (node (ref "Z1") (pin "2") (pinfunction "2_2") (pintype "passive"))
      (node (ref "Z2") (pin "2") (pinfunction "2_2") (pintype "passive"))
    )
    (net (code "24") (name "HWB") (class "Default")
      (node (ref "R4") (pin "1") (pinfunction "1_1") (pintype "passive"))
      (node (ref "U1") (pin "33") (pinfunction "(#HWB)PE2_33") (pintype "bidirectional"))
    )
    (net (code "25") (name "IO8") (class "Default")
      (node (ref "J5") (pin "13") (pinfunction "13_13") (pintype "passive"))
      (node (ref "U1") (pin "28") (pinfunction "(ADC11/PCINT4)PB4_28") (pintype "bidirectional"))
    )
    (net (code "26") (name "IO9*") (class "Default")
      (node (ref "J5") (pin "14") (pinfunction "14_14") (pintype "passive"))
      (node (ref "U1") (pin "29") (pinfunction "(PCINT5/OC1A/#OC4B/ADC12)PB5_29") (pintype "bidirectional"))
    )
    (net (code "27") (name "IO10*") (class "Default")
      (node (ref "J5") (pin "15") (pinfunction "15_15") (pintype "passive"))
      (node (ref "U1") (pin "30") (pinfunction "(PCINT6/OC1B/OC4B/ADC13)PB6_30") (pintype "bidirectional"))
    )
    (net (code "28") (name "IO11*") (class "Default")
      (node (ref "J5") (pin "16") (pinfunction "16_16") (pintype "passive"))
      (node (ref "U1") (pin "12") (pinfunction "(PCINT7/OC0A/OC1C/#RTS)PB7_12") (pintype "bidirectional"))
    )
    (net (code "29") (name "IO12*") (class "Default")
      (node (ref "J5") (pin "17") (pinfunction "17_17") (pintype "passive"))
      (node (ref "U1") (pin "26") (pinfunction "(T1/#OC4D/ADC9)PD6_26") (pintype "bidirectional"))
    )
    (net (code "30") (name "IO13") (class "Default")
      (node (ref "J6") (pin "17") (pinfunction "17_17") (pintype "passive"))
      (node (ref "R8") (pin "1") (pinfunction "1_1") (pintype "passive"))
      (node (ref "U1") (pin "32") (pinfunction "(ICP3/CLK0/OC4A)PC7_32") (pintype "bidirectional"))
    )
    (net (code "31") (name "MISO") (class "Default")
      (node (ref "J6") (pin "2") (pinfunction "2_2") (pintype "passive"))
      (node (ref "U1") (pin "11") (pinfunction "(PD0/MISO/PCINT3)PB3_11") (pintype "bidirectional"))
    )
    (net (code "32") (name "MOSI") (class "Default")
      (node (ref "J5") (pin "1") (pinfunction "1_1") (pintype "passive"))
      (node (ref "U1") (pin "10") (pinfunction "(PDI/MOSI/PCINT2)PB2_10") (pintype "bidirectional"))
    )
    (net (code "33") (name "Net-(C8-Pad1)") (class "Default")
      (node (ref "C8") (pin "1") (pinfunction "1_1") (pintype "passive"))
      (node (ref "CN1") (pin "VBUS") (pinfunction "VBUS_VBUS") (pintype "power_in"))
      (node (ref "F1") (pin "1") (pinfunction "1_1") (pintype "passive"))
    )
    (net (code "34") (name "Net-(C18-Pad1)") (class "Default")
      (node (ref "C18") (pin "1") (pinfunction "1_1") (pintype "passive"))
      (node (ref "L4") (pin "1") (pinfunction "1_1") (pintype "passive"))
      (node (ref "U$11") (pin "RF") (pinfunction "RF_RF") (pintype "bidirectional"))
    )
    (net (code "35") (name "Net-(L-PadA)") (class "Default")
      (node (ref "L") (pin "A") (pinfunction "A_A") (pintype "passive"))
      (node (ref "R8") (pin "2") (pinfunction "2_2") (pintype "passive"))
    )
    (net (code "36") (name "Net-(ON-PadA)") (class "Default")
      (node (ref "ON") (pin "A") (pinfunction "A_A") (pintype "passive"))
      (node (ref "R5") (pin "2") (pinfunction "2_2") (pintype "passive"))
    )
    (net (code "37") (name "Net-(Q1-1)") (class "Default")
      (node (ref "Q1") (pin "P$1") (pinfunction "1_P$1") (pintype "passive"))
      (node (ref "U1") (pin "16") (pinfunction "XTAL2_16") (pintype "bidirectional"))
    )
    (net (code "38") (name "Net-(Q1-3)") (class "Default")
      (node (ref "Q1") (pin "P$3") (pinfunction "3_P$3") (pintype "passive"))
      (node (ref "U1") (pin "17") (pinfunction "XTAL1_17") (pintype "bidirectional"))
    )
    (net (code "39") (name "Net-(R6-Pad2)") (class "Default")
      (node (ref "R6") (pin "2") (pinfunction "2_2") (pintype "passive"))
      (node (ref "TX") (pin "A") (pinfunction "A_A") (pintype "passive"))
    )
    (net (code "40") (name "Net-(R7-Pad2)") (class "Default")
      (node (ref "R7") (pin "2") (pinfunction "2_2") (pintype "passive"))
      (node (ref "RX") (pin "A") (pinfunction "A_A") (pintype "passive"))
    )
    (net (code "41") (name "Net-(U1-AVCC1)") (class "Default")
      (node (ref "C7") (pin "1") (pinfunction "1_1") (pintype "passive"))
      (node (ref "L2") (pin "2") (pinfunction "2_2") (pintype "passive"))
      (node (ref "U1") (pin "44") (pinfunction "AVCC1_44") (pintype "power_in"))
    )
    (net (code "42") (name "Net-(U5-EXT_RSTB)") (class "Default")
      (node (ref "RST") (pin "2") (pinfunction "2_2") (pintype "passive"))
      (node (ref "U5") (pin "32") (pinfunction "EXT_RSTB_32") (pintype "bidirectional"))
    )
    (net (code "43") (name "Net-(U5-GPIO0)") (class "Default")
      (node (ref "LOAD/OTA") (pin "2") (pinfunction "2_2") (pintype "passive"))
      (node (ref "R10") (pin "1") (pinfunction "1_1") (pintype "passive"))
      (node (ref "TP3") (pin "TP") (pinfunction "TP_TP") (pintype "input"))
      (node (ref "U5") (pin "15") (pinfunction "GPIO0_15") (pintype "bidirectional"))
    )
    (net (code "44") (name "Net-(U5-LNA)") (class "Default")
      (node (ref "C18") (pin "2") (pinfunction "2_2") (pintype "passive"))
      (node (ref "L5") (pin "1") (pinfunction "1_1") (pintype "passive"))
      (node (ref "U5") (pin "2") (pinfunction "LNA_2") (pintype "passive"))
    )
    (net (code "45") (name "Net-(U5-RES12K)") (class "Default")
      (node (ref "R3") (pin "1") (pinfunction "1_1") (pintype "passive"))
      (node (ref "U5") (pin "31") (pinfunction "RES12K_31") (pintype "passive"))
    )
    (net (code "46") (name "Net-(U5-SD_CLK)") (class "Default")
      (node (ref "R13") (pin "2") (pinfunction "2_2") (pintype "passive"))
      (node (ref "U5") (pin "21") (pinfunction "SD_CLK_21") (pintype "bidirectional"))
    )
    (net (code "47") (name "Net-(U5-SD_CMD)") (class "Default")
      (node (ref "U5") (pin "20") (pinfunction "SD_CMD_20") (pintype "bidirectional"))
      (node (ref "U6") (pin "1") (pinfunction "/CS_1") (pintype "input"))
    )
    (net (code "48") (name "Net-(U5-SD_DATA_0)") (class "Default")
      (node (ref "U5") (pin "22") (pinfunction "SD_DATA_0_22") (pintype "bidirectional"))
      (node (ref "U6") (pin "2") (pinfunction "D0_2") (pintype "output"))
    )
    (net (code "49") (name "Net-(U5-SD_DATA_1)") (class "Default")
      (node (ref "U5") (pin "23") (pinfunction "SD_DATA_1_23") (pintype "bidirectional"))
      (node (ref "U6") (pin "5") (pinfunction "DIO_5") (pintype "bidirectional"))
    )
    (net (code "50") (name "Net-(U5-SD_DATA_2)") (class "Default")
      (node (ref "U5") (pin "18") (pinfunction "SD_DATA_2_18") (pintype "bidirectional"))
      (node (ref "U6") (pin "7") (pinfunction "/HOLD_7") (pintype "input"))
    )
    (net (code "51") (name "Net-(U5-SD_DATA_3)") (class "Default")
      (node (ref "U5") (pin "19") (pinfunction "SD_DATA_3_19") (pintype "bidirectional"))
      (node (ref "U6") (pin "3") (pinfunction "/WP_3") (pintype "input"))
    )
    (net (code "52") (name "Net-(U5-XTAL_IN)") (class "Default")
      (node (ref "C17") (pin "1") (pinfunction "1_1") (pintype "passive"))
      (node (ref "U5") (pin "28") (pinfunction "XTAL_IN_28") (pintype "passive"))
      (node (ref "Y1") (pin "1") (pinfunction "C1_1") (pintype "passive"))
    )
    (net (code "53") (name "Net-(U5-XTAL_OUT)") (class "Default")
      (node (ref "C16") (pin "1") (pinfunction "1_1") (pintype "passive"))
      (node (ref "U5") (pin "27") (pinfunction "XTAL_OUT_27") (pintype "passive"))
      (node (ref "Y1") (pin "3") (pinfunction "C2_3") (pintype "passive"))
    )
    (net (code "54") (name "Net-(U6-CLK)") (class "Default")
      (node (ref "R13") (pin "1") (pinfunction "1_1") (pintype "passive"))
      (node (ref "U6") (pin "6") (pinfunction "CLK_6") (pintype "input"))
    )
    (net (code "55") (name "RD+") (class "Default")
      (node (ref "RN1") (pin "3") (pinfunction "2_3") (pintype "passive"))
      (node (ref "U1") (pin "4") (pinfunction "D+_4") (pintype "bidirectional"))
    )
    (net (code "56") (name "RD-") (class "Default")
      (node (ref "RN1") (pin "4") (pinfunction "2_4") (pintype "passive"))
      (node (ref "U1") (pin "3") (pinfunction "D-_3") (pintype "bidirectional"))
    )
    (net (code "57") (name "RESET") (class "Default")
      (node (ref "J5") (pin "5") (pinfunction "5_5") (pintype "passive"))
      (node (ref "J6") (pin "5") (pinfunction "5_5") (pintype "passive"))
      (node (ref "LOAD/OTA") (pin "1") (pinfunction "1_1") (pintype "passive"))
      (node (ref "R1") (pin "2") (pinfunction "2_2") (pintype "passive"))
      (node (ref "RESET") (pin "2") (pinfunction "S_2") (pintype "passive"))
      (node (ref "RESET") (pin "4") (pinfunction "S1_4") (pintype "passive"))
      (node (ref "U1") (pin "13") (pinfunction "RESET_13") (pintype "input"))
    )
    (net (code "58") (name "RXLED{slash}SS") (class "Default")
      (node (ref "J5") (pin "2") (pinfunction "2_2") (pintype "passive"))
      (node (ref "R7") (pin "1") (pinfunction "1_1") (pintype "passive"))
      (node (ref "U1") (pin "8") (pinfunction "(SS/PCINT0)PB0_8") (pintype "bidirectional"))
    )
    (net (code "59") (name "SCK") (class "Default")
      (node (ref "J6") (pin "1") (pinfunction "1_1") (pintype "passive"))
      (node (ref "U1") (pin "9") (pinfunction "(SCLK/PCINT1)PB1_9") (pintype "bidirectional"))
    )
    (net (code "60") (name "TXLED") (class "Default")
      (node (ref "R6") (pin "1") (pinfunction "1_1") (pintype "passive"))
      (node (ref "U1") (pin "22") (pinfunction "(XCK1/#CTS)PD5_22") (pintype "bidirectional"))
    )
    (net (code "61") (name "UCAP") (class "Default")
      (node (ref "C5") (pin "1") (pinfunction "1_1") (pintype "passive"))
      (node (ref "U1") (pin "6") (pinfunction "UCAP_6") (pintype "passive"))
    )
    (net (code "62") (name "VDD") (class "Default")
      (node (ref "U5") (pin "16") (pinfunction "VDD_16") (pintype "power_in"))
    )
    (net (code "63") (name "VDD_RTC") (class "Default")
      (node (ref "U5") (pin "5") (pinfunction "VDD_RTC_5") (pintype "power_in"))
    )
    (net (code "64") (name "VIN") (class "Default")
      (node (ref "C4") (pin "1") (pinfunction "1_1") (pintype "passive"))
      (node (ref "J6") (pin "3") (pinfunction "3_3") (pintype "passive"))
      (node (ref "R9") (pin "2") (pinfunction "2_2") (pintype "passive"))
      (node (ref "T1") (pin "3") (pinfunction "G_3") (pintype "passive"))
      (node (ref "U3") (pin "3") (pinfunction "IN_3") (pintype "bidirectional"))
    )
    (net (code "65") (name "VUSB") (class "Default")
      (node (ref "C9") (pin "1") (pinfunction "1_1") (pintype "passive"))
      (node (ref "F1") (pin "2") (pinfunction "2_2") (pintype "passive"))
      (node (ref "R2") (pin "2") (pinfunction "2_2") (pintype "passive"))
      (node (ref "T1") (pin "1") (pinfunction "D_1") (pintype "passive"))
      (node (ref "U1") (pin "7") (pinfunction "VBUS_7") (pintype "input"))
    )
    (net (code "66") (name "unconnected-(CN1-PadID)") (class "Default")
      (node (ref "CN1") (pin "ID") (pinfunction "ID_ID") (pintype "bidirectional"))
    )
    (net (code "67") (name "unconnected-(U5-MTCK-Pad12)") (class "Default")
      (node (ref "U5") (pin "12") (pinfunction "MTCK_12") (pintype "bidirectional"))
    )
    (net (code "68") (name "unconnected-(U5-MTDI-Pad10)") (class "Default")
      (node (ref "U5") (pin "10") (pinfunction "MTDI_10") (pintype "bidirectional"))
    )
    (net (code "69") (name "unconnected-(U5-MTMS-Pad9)") (class "Default")
      (node (ref "U5") (pin "9") (pinfunction "MTMS_9") (pintype "bidirectional"))
    )
    (net (code "70") (name "unconnected-(U5-TOUT-Pad6)") (class "Default")
      (node (ref "U5") (pin "6") (pinfunction "TOUT_6") (pintype "passive"))
    )
  )
)
